# teensy_shield.net
KiCad netlist of a schematic drawn in EAGLE
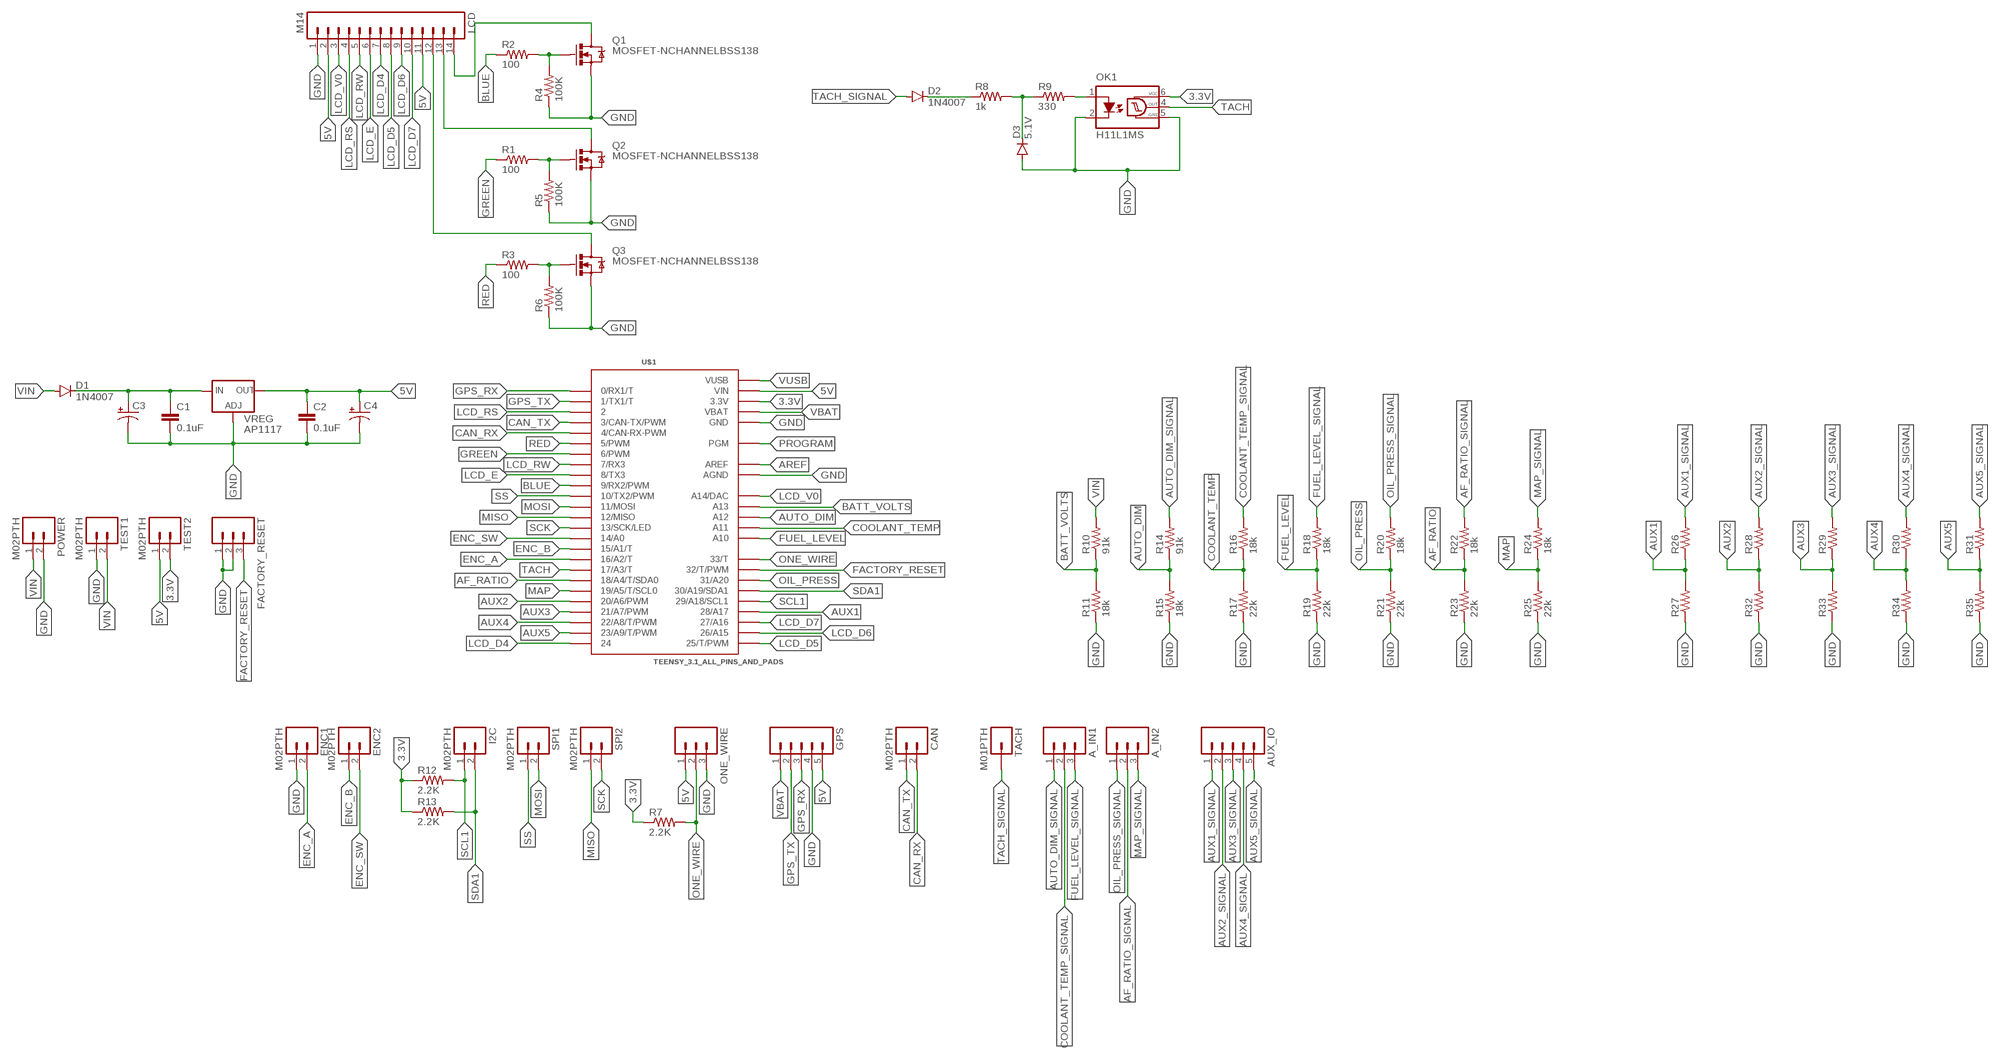
[diagram p0: schematic, sheet 1]

(export (version "E")
  (design (tool "Eeschema 10.0.6"))
  (components
    (comp (ref "AUX_IO")
      (value "M05PTH")
      (footprint "eagle-import:1X05")
      (libsource (lib "eagle-import") (part "M05PTH"))
    )
    (comp (ref "A_IN1")
      (value "M03PTH")
      (footprint "eagle-import:1X03")
      (libsource (lib "eagle-import") (part "M03PTH"))
    )
    (comp (ref "A_IN2")
      (value "M03PTH")
      (footprint "eagle-import:1X03")
      (libsource (lib "eagle-import") (part "M03PTH"))
    )
    (comp (ref "C1")
      (value "0.1uF")
      (footprint "eagle-import:1206")
      (libsource (lib "eagle-import") (part "CAP1206"))
    )
    (comp (ref "C2")
      (value "0.1uF")
      (footprint "eagle-import:1206")
      (libsource (lib "eagle-import") (part "CAP1206"))
    )
    (comp (ref "C3")
      (value "CAP_POL6032")
      (footprint "eagle-import:EIA6032")
      (libsource (lib "eagle-import") (part "CAP_POL6032"))
    )
    (comp (ref "C4")
      (value "CAP_POL6032")
      (footprint "eagle-import:EIA6032")
      (libsource (lib "eagle-import") (part "CAP_POL6032"))
    )
    (comp (ref "CAN")
      (value "M02PTH")
      (footprint "eagle-import:1X02")
      (libsource (lib "eagle-import") (part "M02PTH"))
    )
    (comp (ref "D1")
      (value "1N4007")
      (footprint "eagle-import:SMA-DIODE_ALT")
      (libsource (lib "eagle-import") (part "DIODESMA-ALT"))
    )
    (comp (ref "D2")
      (value "1N4007")
      (footprint "eagle-import:SMA-DIODE_ALT")
      (libsource (lib "eagle-import") (part "DIODESMA-ALT"))
    )
    (comp (ref "D3")
      (value "5.1V")
      (footprint "eagle-import:SMA-DIODE_ALT")
      (libsource (lib "eagle-import") (part "DIODESMA-ALT"))
    )
    (comp (ref "ENC1")
      (value "M02PTH")
      (footprint "eagle-import:1X02")
      (libsource (lib "eagle-import") (part "M02PTH"))
    )
    (comp (ref "ENC2")
      (value "M02PTH")
      (footprint "eagle-import:1X02")
      (libsource (lib "eagle-import") (part "M02PTH"))
    )
    (comp (ref "FACTORY_RESET")
      (value "M03PTH")
      (footprint "eagle-import:1X03")
      (libsource (lib "eagle-import") (part "M03PTH"))
    )
    (comp (ref "GPS")
      (value "M05PTH")
      (footprint "eagle-import:1X05")
      (libsource (lib "eagle-import") (part "M05PTH"))
    )
    (comp (ref "I2C")
      (value "M02PTH")
      (footprint "eagle-import:1X02")
      (libsource (lib "eagle-import") (part "M02PTH"))
    )
    (comp (ref "LCD")
      (value "M14")
      (footprint "eagle-import:1X14")
      (libsource (lib "eagle-import") (part "M14"))
    )
    (comp (ref "OK1")
      (value "H11L1MS")
      (footprint "eagle-import:DIL6-SMD")
      (libsource (lib "eagle-import") (part "H11LMS1"))
    )
    (comp (ref "ONE_WIRE")
      (value "M03PTH")
      (footprint "eagle-import:1X03")
      (libsource (lib "eagle-import") (part "M03PTH"))
    )
    (comp (ref "POWER")
      (value "M02PTH")
      (footprint "eagle-import:1X02")
      (libsource (lib "eagle-import") (part "M02PTH"))
    )
    (comp (ref "Q1")
      (value "MOSFET-NCHANNELBSS138")
      (footprint "eagle-import:SOT23")
      (libsource (lib "eagle-import") (part "MOSFET-NCHANNELBSS138"))
    )
    (comp (ref "Q2")
      (value "MOSFET-NCHANNELBSS138")
      (footprint "eagle-import:SOT23")
      (libsource (lib "eagle-import") (part "MOSFET-NCHANNELBSS138"))
    )
    (comp (ref "Q3")
      (value "MOSFET-NCHANNELBSS138")
      (footprint "eagle-import:SOT23")
      (libsource (lib "eagle-import") (part "MOSFET-NCHANNELBSS138"))
    )
    (comp (ref "R1")
      (value "100")
      (footprint "eagle-import:1206")
      (libsource (lib "eagle-import") (part "RESISTOR1206"))
    )
    (comp (ref "R2")
      (value "100")
      (footprint "eagle-import:1206")
      (libsource (lib "eagle-import") (part "RESISTOR1206"))
    )
    (comp (ref "R3")
      (value "100")
      (footprint "eagle-import:1206")
      (libsource (lib "eagle-import") (part "RESISTOR1206"))
    )
    (comp (ref "R4")
      (value "100K")
      (footprint "eagle-import:1206")
      (libsource (lib "eagle-import") (part "RESISTOR1206"))
    )
    (comp (ref "R5")
      (value "100K")
      (footprint "eagle-import:1206")
      (libsource (lib "eagle-import") (part "RESISTOR1206"))
    )
    (comp (ref "R6")
      (value "100K")
      (footprint "eagle-import:1206")
      (libsource (lib "eagle-import") (part "RESISTOR1206"))
    )
    (comp (ref "R7")
      (value "2.2K")
      (footprint "eagle-import:1206")
      (libsource (lib "eagle-import") (part "RESISTOR1206"))
    )
    (comp (ref "R8")
      (value "1k")
      (footprint "eagle-import:1206")
      (libsource (lib "eagle-import") (part "RESISTOR1206"))
    )
    (comp (ref "R9")
      (value "330")
      (footprint "eagle-import:1206")
      (libsource (lib "eagle-import") (part "RESISTOR1206"))
    )
    (comp (ref "R10")
      (value "91k")
      (footprint "eagle-import:1206")
      (libsource (lib "eagle-import") (part "RESISTOR1206"))
    )
    (comp (ref "R11")
      (value "18k")
      (footprint "eagle-import:1206")
      (libsource (lib "eagle-import") (part "RESISTOR1206"))
    )
    (comp (ref "R12")
      (value "2.2K")
      (footprint "eagle-import:1206")
      (libsource (lib "eagle-import") (part "RESISTOR1206"))
    )
    (comp (ref "R13")
      (value "2.2K")
      (footprint "eagle-import:1206")
      (libsource (lib "eagle-import") (part "RESISTOR1206"))
    )
    (comp (ref "R14")
      (value "91k")
      (footprint "eagle-import:1206")
      (libsource (lib "eagle-import") (part "RESISTOR1206"))
    )
    (comp (ref "R15")
      (value "18k")
      (footprint "eagle-import:1206")
      (libsource (lib "eagle-import") (part "RESISTOR1206"))
    )
    (comp (ref "R16")
      (value "18k")
      (footprint "eagle-import:1206")
      (libsource (lib "eagle-import") (part "RESISTOR1206"))
    )
    (comp (ref "R17")
      (value "22k")
      (footprint "eagle-import:1206")
      (libsource (lib "eagle-import") (part "RESISTOR1206"))
    )
    (comp (ref "R18")
      (value "18k")
      (footprint "eagle-import:1206")
      (libsource (lib "eagle-import") (part "RESISTOR1206"))
    )
    (comp (ref "R19")
      (value "22k")
      (footprint "eagle-import:1206")
      (libsource (lib "eagle-import") (part "RESISTOR1206"))
    )
    (comp (ref "R20")
      (value "18k")
      (footprint "eagle-import:1206")
      (libsource (lib "eagle-import") (part "RESISTOR1206"))
    )
    (comp (ref "R21")
      (value "22k")
      (footprint "eagle-import:1206")
      (libsource (lib "eagle-import") (part "RESISTOR1206"))
    )
    (comp (ref "R22")
      (value "18k")
      (footprint "eagle-import:1206")
      (libsource (lib "eagle-import") (part "RESISTOR1206"))
    )
    (comp (ref "R23")
      (value "22k")
      (footprint "eagle-import:1206")
      (libsource (lib "eagle-import") (part "RESISTOR1206"))
    )
    (comp (ref "R24")
      (value "18k")
      (footprint "eagle-import:1206")
      (libsource (lib "eagle-import") (part "RESISTOR1206"))
    )
    (comp (ref "R25")
      (value "22k")
      (footprint "eagle-import:1206")
      (libsource (lib "eagle-import") (part "RESISTOR1206"))
    )
    (comp (ref "R26")
      (value "RESISTOR1206")
      (footprint "eagle-import:1206")
      (libsource (lib "eagle-import") (part "RESISTOR1206"))
    )
    (comp (ref "R27")
      (value "RESISTOR1206")
      (footprint "eagle-import:1206")
      (libsource (lib "eagle-import") (part "RESISTOR1206"))
    )
    (comp (ref "R28")
      (value "RESISTOR1206")
      (footprint "eagle-import:1206")
      (libsource (lib "eagle-import") (part "RESISTOR1206"))
    )
    (comp (ref "R29")
      (value "RESISTOR1206")
      (footprint "eagle-import:1206")
      (libsource (lib "eagle-import") (part "RESISTOR1206"))
    )
    (comp (ref "R30")
      (value "RESISTOR1206")
      (footprint "eagle-import:1206")
      (libsource (lib "eagle-import") (part "RESISTOR1206"))
    )
    (comp (ref "R31")
      (value "RESISTOR1206")
      (footprint "eagle-import:1206")
      (libsource (lib "eagle-import") (part "RESISTOR1206"))
    )
    (comp (ref "R32")
      (value "RESISTOR1206")
      (footprint "eagle-import:1206")
      (libsource (lib "eagle-import") (part "RESISTOR1206"))
    )
    (comp (ref "R33")
      (value "RESISTOR1206")
      (footprint "eagle-import:1206")
      (libsource (lib "eagle-import") (part "RESISTOR1206"))
    )
    (comp (ref "R34")
      (value "RESISTOR1206")
      (footprint "eagle-import:1206")
      (libsource (lib "eagle-import") (part "RESISTOR1206"))
    )
    (comp (ref "R35")
      (value "RESISTOR1206")
      (footprint "eagle-import:1206")
      (libsource (lib "eagle-import") (part "RESISTOR1206"))
    )
    (comp (ref "SPI1")
      (value "M02PTH")
      (footprint "eagle-import:1X02")
      (libsource (lib "eagle-import") (part "M02PTH"))
    )
    (comp (ref "SPI2")
      (value "M02PTH")
      (footprint "eagle-import:1X02")
      (libsource (lib "eagle-import") (part "M02PTH"))
    )
    (comp (ref "TACH")
      (value "M01PTH")
      (footprint "eagle-import:1X01")
      (libsource (lib "eagle-import") (part "M01PTH"))
    )
    (comp (ref "TEST1")
      (value "M02PTH")
      (footprint "eagle-import:1X02")
      (libsource (lib "eagle-import") (part "M02PTH"))
    )
    (comp (ref "TEST2")
      (value "M02PTH")
      (footprint "eagle-import:1X02")
      (libsource (lib "eagle-import") (part "M02PTH"))
    )
    (comp (ref "U$1")
      (value "TEENSY_3.1_ALL_PINS_AND_PADS")
      (footprint "eagle-import:TEENSY_3.1_ALLPINS")
      (libsource (lib "eagle-import") (part "TEENSY_3.1_ALL_PINS_AND_PADS"))
    )
    (comp (ref "VREG")
      (value "AP1117")
      (footprint "eagle-import:SOT223")
      (libsource (lib "eagle-import") (part "V_REG_317SMD"))
    )
  )
  (nets
    (net (code "1") (name "3.3V") (class "Default")
      (node (ref "OK1") (pin "6") (pinfunction "VCC_6") (pintype "power_in"))
      (node (ref "R12") (pin "1") (pinfunction "1_1") (pintype "passive"))
      (node (ref "R13") (pin "1") (pinfunction "1_1") (pintype "passive"))
      (node (ref "R7") (pin "1") (pinfunction "1_1") (pintype "passive"))
      (node (ref "TEST2") (pin "2") (pinfunction "2_2") (pintype "passive"))
      (node (ref "U$1") (pin "3.3V") (pinfunction "3.3V_3.3V") (pintype "power_in"))
      (node (ref "U$1") (pin "3.3V1") (pinfunction "3.3V_3.3V1") (pintype "power_in"))
      (node (ref "U$1") (pin "3.3V2") (pinfunction "3.3V_3.3V2") (pintype "power_in"))
    )
    (net (code "2") (name "5V") (class "Default")
      (node (ref "C2") (pin "1") (pinfunction "1_1") (pintype "passive"))
      (node (ref "C4") (pin "P$1") (pinfunction "+_P$1") (pintype "passive"))
      (node (ref "GPS") (pin "5") (pinfunction "5_5") (pintype "passive"))
      (node (ref "LCD") (pin "11") (pinfunction "11_11") (pintype "passive"))
      (node (ref "LCD") (pin "2") (pinfunction "2_2") (pintype "passive"))
      (node (ref "ONE_WIRE") (pin "1") (pinfunction "1_1") (pintype "passive"))
      (node (ref "TEST2") (pin "1") (pinfunction "1_1") (pintype "passive"))
      (node (ref "U$1") (pin "VIN") (pinfunction "VIN_VIN") (pintype "power_in"))
      (node (ref "VREG") (pin "2") (pinfunction "OUT_2") (pintype "output"))
    )
    (net (code "3") (name "AF_RATIO") (class "Default")
      (node (ref "R22") (pin "1") (pinfunction "1_1") (pintype "passive"))
      (node (ref "R23") (pin "2") (pinfunction "2_2") (pintype "passive"))
      (node (ref "U$1") (pin "18/A4") (pinfunction "18/A4/T/SDA0_18/A4") (pintype "bidirectional"))
    )
    (net (code "4") (name "AF_RATIO_SIGNAL") (class "Default")
      (node (ref "A_IN2") (pin "2") (pinfunction "2_2") (pintype "passive"))
      (node (ref "R22") (pin "2") (pinfunction "2_2") (pintype "passive"))
    )
    (net (code "5") (name "AREF") (class "Default")
      (node (ref "U$1") (pin "AREF") (pinfunction "AREF_AREF") (pintype "power_in"))
    )
    (net (code "6") (name "AUTO_DIM") (class "Default")
      (node (ref "R14") (pin "1") (pinfunction "1_1") (pintype "passive"))
      (node (ref "R15") (pin "2") (pinfunction "2_2") (pintype "passive"))
      (node (ref "U$1") (pin "A12") (pinfunction "A12_A12") (pintype "bidirectional"))
    )
    (net (code "7") (name "AUTO_DIM_SIGNAL") (class "Default")
      (node (ref "A_IN1") (pin "1") (pinfunction "1_1") (pintype "passive"))
      (node (ref "R14") (pin "2") (pinfunction "2_2") (pintype "passive"))
    )
    (net (code "8") (name "AUX1") (class "Default")
      (node (ref "R26") (pin "1") (pinfunction "1_1") (pintype "passive"))
      (node (ref "R27") (pin "2") (pinfunction "2_2") (pintype "passive"))
      (node (ref "U$1") (pin "28") (pinfunction "28/A17_28") (pintype "bidirectional"))
    )
    (net (code "9") (name "AUX1_SIGNAL") (class "Default")
      (node (ref "AUX_IO") (pin "1") (pinfunction "1_1") (pintype "passive"))
      (node (ref "R26") (pin "2") (pinfunction "2_2") (pintype "passive"))
    )
    (net (code "10") (name "AUX2") (class "Default")
      (node (ref "R28") (pin "1") (pinfunction "1_1") (pintype "passive"))
      (node (ref "R32") (pin "2") (pinfunction "2_2") (pintype "passive"))
      (node (ref "U$1") (pin "20/A6") (pinfunction "20/A6/PWM_20/A6") (pintype "bidirectional"))
    )
    (net (code "11") (name "AUX2_SIGNAL") (class "Default")
      (node (ref "AUX_IO") (pin "2") (pinfunction "2_2") (pintype "passive"))
      (node (ref "R28") (pin "2") (pinfunction "2_2") (pintype "passive"))
    )
    (net (code "12") (name "AUX3") (class "Default")
      (node (ref "R29") (pin "1") (pinfunction "1_1") (pintype "passive"))
      (node (ref "R33") (pin "2") (pinfunction "2_2") (pintype "passive"))
      (node (ref "U$1") (pin "21/A7") (pinfunction "21/A7/PWM_21/A7") (pintype "bidirectional"))
    )
    (net (code "13") (name "AUX3_SIGNAL") (class "Default")
      (node (ref "AUX_IO") (pin "3") (pinfunction "3_3") (pintype "passive"))
      (node (ref "R29") (pin "2") (pinfunction "2_2") (pintype "passive"))
    )
    (net (code "14") (name "AUX4") (class "Default")
      (node (ref "R30") (pin "1") (pinfunction "1_1") (pintype "passive"))
      (node (ref "R34") (pin "2") (pinfunction "2_2") (pintype "passive"))
      (node (ref "U$1") (pin "22/A8") (pinfunction "22/A8/T/PWM_22/A8") (pintype "bidirectional"))
    )
    (net (code "15") (name "AUX4_SIGNAL") (class "Default")
      (node (ref "AUX_IO") (pin "4") (pinfunction "4_4") (pintype "passive"))
      (node (ref "R30") (pin "2") (pinfunction "2_2") (pintype "passive"))
    )
    (net (code "16") (name "AUX5") (class "Default")
      (node (ref "R31") (pin "1") (pinfunction "1_1") (pintype "passive"))
      (node (ref "R35") (pin "2") (pinfunction "2_2") (pintype "passive"))
      (node (ref "U$1") (pin "23/A9") (pinfunction "23/A9/T/PWM_23/A9") (pintype "bidirectional"))
    )
    (net (code "17") (name "AUX5_SIGNAL") (class "Default")
      (node (ref "AUX_IO") (pin "5") (pinfunction "5_5") (pintype "passive"))
      (node (ref "R31") (pin "2") (pinfunction "2_2") (pintype "passive"))
    )
    (net (code "18") (name "BATT_VOLTS") (class "Default")
      (node (ref "R10") (pin "1") (pinfunction "1_1") (pintype "passive"))
      (node (ref "R11") (pin "2") (pinfunction "2_2") (pintype "passive"))
      (node (ref "U$1") (pin "A13") (pinfunction "A13_A13") (pintype "bidirectional"))
    )
    (net (code "19") (name "BLUE") (class "Default")
      (node (ref "R2") (pin "1") (pinfunction "1_1") (pintype "passive"))
      (node (ref "U$1") (pin "9") (pinfunction "9/RX2/PWM_9") (pintype "bidirectional"))
    )
    (net (code "20") (name "CAN_RX") (class "Default")
      (node (ref "CAN") (pin "2") (pinfunction "2_2") (pintype "passive"))
      (node (ref "U$1") (pin "4") (pinfunction "4/CAN-RX-PWM_4") (pintype "bidirectional"))
    )
    (net (code "21") (name "CAN_TX") (class "Default")
      (node (ref "CAN") (pin "1") (pinfunction "1_1") (pintype "passive"))
      (node (ref "U$1") (pin "3") (pinfunction "3/CAN-TX/PWM_3") (pintype "bidirectional"))
    )
    (net (code "22") (name "COOLANT_TEMP") (class "Default")
      (node (ref "R16") (pin "1") (pinfunction "1_1") (pintype "passive"))
      (node (ref "R17") (pin "2") (pinfunction "2_2") (pintype "passive"))
      (node (ref "U$1") (pin "A11") (pinfunction "A11_A11") (pintype "bidirectional"))
    )
    (net (code "23") (name "COOLANT_TEMP_SIGNAL") (class "Default")
      (node (ref "A_IN1") (pin "2") (pinfunction "2_2") (pintype "passive"))
      (node (ref "R16") (pin "2") (pinfunction "2_2") (pintype "passive"))
    )
    (net (code "24") (name "ENC_A") (class "Default")
      (node (ref "ENC1") (pin "2") (pinfunction "2_2") (pintype "passive"))
      (node (ref "U$1") (pin "16/A2") (pinfunction "16/A2/T_16/A2") (pintype "bidirectional"))
    )
    (net (code "25") (name "ENC_B") (class "Default")
      (node (ref "ENC2") (pin "1") (pinfunction "1_1") (pintype "passive"))
      (node (ref "U$1") (pin "15/A1") (pinfunction "15/A1/T_15/A1") (pintype "bidirectional"))
    )
    (net (code "26") (name "ENC_SW") (class "Default")
      (node (ref "ENC2") (pin "2") (pinfunction "2_2") (pintype "passive"))
      (node (ref "U$1") (pin "14/A0") (pinfunction "14/A0_14/A0") (pintype "bidirectional"))
    )
    (net (code "27") (name "FACTORY_RESET") (class "Default")
      (node (ref "FACTORY_RESET") (pin "3") (pinfunction "3_3") (pintype "passive"))
      (node (ref "U$1") (pin "32") (pinfunction "32/T/PWM_32") (pintype "bidirectional"))
    )
    (net (code "28") (name "FUEL_LEVEL") (class "Default")
      (node (ref "R18") (pin "1") (pinfunction "1_1") (pintype "passive"))
      (node (ref "R19") (pin "2") (pinfunction "2_2") (pintype "passive"))
      (node (ref "U$1") (pin "A10") (pinfunction "A10_A10") (pintype "bidirectional"))
    )
    (net (code "29") (name "FUEL_LEVEL_SIGNAL") (class "Default")
      (node (ref "A_IN1") (pin "3") (pinfunction "3_3") (pintype "passive"))
      (node (ref "R18") (pin "2") (pinfunction "2_2") (pintype "passive"))
    )
    (net (code "30") (name "GND") (class "Default")
      (node (ref "C1") (pin "2") (pinfunction "2_2") (pintype "passive"))
      (node (ref "C2") (pin "2") (pinfunction "2_2") (pintype "passive"))
      (node (ref "C3") (pin "P$2") (pinfunction "-_P$2") (pintype "passive"))
      (node (ref "C4") (pin "P$2") (pinfunction "-_P$2") (pintype "passive"))
      (node (ref "D3") (pin "A") (pinfunction "A_A") (pintype "passive"))
      (node (ref "ENC1") (pin "1") (pinfunction "1_1") (pintype "passive"))
      (node (ref "FACTORY_RESET") (pin "1") (pinfunction "1_1") (pintype "passive"))
      (node (ref "FACTORY_RESET") (pin "2") (pinfunction "2_2") (pintype "passive"))
      (node (ref "GPS") (pin "4") (pinfunction "4_4") (pintype "passive"))
      (node (ref "LCD") (pin "1") (pinfunction "1_1") (pintype "passive"))
      (node (ref "OK1") (pin "2") (pinfunction "C_2") (pintype "passive"))
      (node (ref "OK1") (pin "5") (pinfunction "GND_5") (pintype "power_in"))
      (node (ref "ONE_WIRE") (pin "3") (pinfunction "3_3") (pintype "passive"))
      (node (ref "POWER") (pin "2") (pinfunction "2_2") (pintype "passive"))
      (node (ref "Q1") (pin "2") (pinfunction "S_2") (pintype "passive"))
      (node (ref "Q2") (pin "2") (pinfunction "S_2") (pintype "passive"))
      (node (ref "Q3") (pin "2") (pinfunction "S_2") (pintype "passive"))
      (node (ref "R11") (pin "1") (pinfunction "1_1") (pintype "passive"))
      (node (ref "R15") (pin "1") (pinfunction "1_1") (pintype "passive"))
      (node (ref "R17") (pin "1") (pinfunction "1_1") (pintype "passive"))
      (node (ref "R19") (pin "1") (pinfunction "1_1") (pintype "passive"))
      (node (ref "R21") (pin "1") (pinfunction "1_1") (pintype "passive"))
      (node (ref "R23") (pin "1") (pinfunction "1_1") (pintype "passive"))
      (node (ref "R25") (pin "1") (pinfunction "1_1") (pintype "passive"))
      (node (ref "R27") (pin "1") (pinfunction "1_1") (pintype "passive"))
      (node (ref "R32") (pin "1") (pinfunction "1_1") (pintype "passive"))
      (node (ref "R33") (pin "1") (pinfunction "1_1") (pintype "passive"))
      (node (ref "R34") (pin "1") (pinfunction "1_1") (pintype "passive"))
      (node (ref "R35") (pin "1") (pinfunction "1_1") (pintype "passive"))
      (node (ref "R4") (pin "1") (pinfunction "1_1") (pintype "passive"))
      (node (ref "R5") (pin "1") (pinfunction "1_1") (pintype "passive"))
      (node (ref "R6") (pin "1") (pinfunction "1_1") (pintype "passive"))
      (node (ref "TEST1") (pin "1") (pinfunction "1_1") (pintype "passive"))
      (node (ref "U$1") (pin "AGND") (pinfunction "AGND_AGND") (pintype "power_in"))
      (node (ref "U$1") (pin "GND") (pinfunction "GND_GND") (pintype "power_in"))
      (node (ref "U$1") (pin "GND1") (pinfunction "GND_GND1") (pintype "power_in"))
      (node (ref "U$1") (pin "GND2") (pinfunction "GND_GND2") (pintype "power_in"))
      (node (ref "VREG") (pin "1") (pinfunction "ADJ_1") (pintype "input"))
    )
    (net (code "31") (name "GPS_RX") (class "Default")
      (node (ref "GPS") (pin "3") (pinfunction "3_3") (pintype "passive"))
      (node (ref "U$1") (pin "0") (pinfunction "0/RX1/T_0") (pintype "bidirectional"))
    )
    (net (code "32") (name "GPS_TX") (class "Default")
      (node (ref "GPS") (pin "2") (pinfunction "2_2") (pintype "passive"))
      (node (ref "U$1") (pin "1") (pinfunction "1/TX1/T_1") (pintype "bidirectional"))
    )
    (net (code "33") (name "GREEN") (class "Default")
      (node (ref "R1") (pin "1") (pinfunction "1_1") (pintype "passive"))
      (node (ref "U$1") (pin "6") (pinfunction "6/PWM_6") (pintype "bidirectional"))
    )
    (net (code "34") (name "LCD_D4") (class "Default")
      (node (ref "LCD") (pin "7") (pinfunction "7_7") (pintype "passive"))
      (node (ref "U$1") (pin "24") (pinfunction "24_24") (pintype "bidirectional"))
    )
    (net (code "35") (name "LCD_D5") (class "Default")
      (node (ref "LCD") (pin "8") (pinfunction "8_8") (pintype "passive"))
      (node (ref "U$1") (pin "25") (pinfunction "25/T/PWM_25") (pintype "bidirectional"))
    )
    (net (code "36") (name "LCD_D6") (class "Default")
      (node (ref "LCD") (pin "9") (pinfunction "9_9") (pintype "passive"))
      (node (ref "U$1") (pin "26") (pinfunction "26/A15_26") (pintype "bidirectional"))
    )
    (net (code "37") (name "LCD_D7") (class "Default")
      (node (ref "LCD") (pin "10") (pinfunction "10_10") (pintype "passive"))
      (node (ref "U$1") (pin "27") (pinfunction "27/A16_27") (pintype "bidirectional"))
    )
    (net (code "38") (name "LCD_E") (class "Default")
      (node (ref "LCD") (pin "6") (pinfunction "6_6") (pintype "passive"))
      (node (ref "U$1") (pin "8") (pinfunction "8/TX3_8") (pintype "bidirectional"))
    )
    (net (code "39") (name "LCD_RS") (class "Default")
      (node (ref "LCD") (pin "4") (pinfunction "4_4") (pintype "passive"))
      (node (ref "U$1") (pin "2") (pinfunction "2_2") (pintype "bidirectional"))
    )
    (net (code "40") (name "LCD_RW") (class "Default")
      (node (ref "LCD") (pin "5") (pinfunction "5_5") (pintype "passive"))
      (node (ref "U$1") (pin "7") (pinfunction "7/RX3_7") (pintype "bidirectional"))
    )
    (net (code "41") (name "LCD_V0") (class "Default")
      (node (ref "LCD") (pin "3") (pinfunction "3_3") (pintype "passive"))
      (node (ref "U$1") (pin "A14") (pinfunction "A14/DAC_A14") (pintype "bidirectional"))
    )
    (net (code "42") (name "MAP") (class "Default")
      (node (ref "R24") (pin "1") (pinfunction "1_1") (pintype "passive"))
      (node (ref "R25") (pin "2") (pinfunction "2_2") (pintype "passive"))
      (node (ref "U$1") (pin "19/A5") (pinfunction "19/A5/T/SCL0_19/A5") (pintype "bidirectional"))
    )
    (net (code "43") (name "MAP_SIGNAL") (class "Default")
      (node (ref "A_IN2") (pin "3") (pinfunction "3_3") (pintype "passive"))
      (node (ref "R24") (pin "2") (pinfunction "2_2") (pintype "passive"))
    )
    (net (code "44") (name "MISO") (class "Default")
      (node (ref "SPI2") (pin "1") (pinfunction "1_1") (pintype "passive"))
      (node (ref "U$1") (pin "12") (pinfunction "12/MISO_12") (pintype "bidirectional"))
    )
    (net (code "45") (name "MOSI") (class "Default")
      (node (ref "SPI1") (pin "2") (pinfunction "2_2") (pintype "passive"))
      (node (ref "U$1") (pin "11") (pinfunction "11/MOSI_11") (pintype "bidirectional"))
    )
    (net (code "46") (name "Net-(C3-+)") (class "Default")
      (node (ref "C1") (pin "1") (pinfunction "1_1") (pintype "passive"))
      (node (ref "C3") (pin "P$1") (pinfunction "+_P$1") (pintype "passive"))
      (node (ref "D1") (pin "C") (pinfunction "C_C") (pintype "passive"))
      (node (ref "VREG") (pin "3") (pinfunction "IN_3") (pintype "input"))
    )
    (net (code "47") (name "Net-(D2-PadC)") (class "Default")
      (node (ref "D2") (pin "C") (pinfunction "C_C") (pintype "passive"))
      (node (ref "R8") (pin "1") (pinfunction "1_1") (pintype "passive"))
    )
    (net (code "48") (name "Net-(D3-PadC)") (class "Default")
      (node (ref "D3") (pin "C") (pinfunction "C_C") (pintype "passive"))
      (node (ref "R8") (pin "2") (pinfunction "2_2") (pintype "passive"))
      (node (ref "R9") (pin "1") (pinfunction "1_1") (pintype "passive"))
    )
    (net (code "49") (name "Net-(OK1-A)") (class "Default")
      (node (ref "OK1") (pin "1") (pinfunction "A_1") (pintype "passive"))
      (node (ref "R9") (pin "2") (pinfunction "2_2") (pintype "passive"))
    )
    (net (code "50") (name "Net-(Q1-D)") (class "Default")
      (node (ref "LCD") (pin "14") (pinfunction "14_14") (pintype "passive"))
      (node (ref "Q1") (pin "3") (pinfunction "D_3") (pintype "passive"))
    )
    (net (code "51") (name "Net-(Q1-G)") (class "Default")
      (node (ref "Q1") (pin "1") (pinfunction "G_1") (pintype "passive"))
      (node (ref "R2") (pin "2") (pinfunction "2_2") (pintype "passive"))
      (node (ref "R4") (pin "2") (pinfunction "2_2") (pintype "passive"))
    )
    (net (code "52") (name "Net-(Q2-D)") (class "Default")
      (node (ref "LCD") (pin "13") (pinfunction "13_13") (pintype "passive"))
      (node (ref "Q2") (pin "3") (pinfunction "D_3") (pintype "passive"))
    )
    (net (code "53") (name "Net-(Q2-G)") (class "Default")
      (node (ref "Q2") (pin "1") (pinfunction "G_1") (pintype "passive"))
      (node (ref "R1") (pin "2") (pinfunction "2_2") (pintype "passive"))
      (node (ref "R5") (pin "2") (pinfunction "2_2") (pintype "passive"))
    )
    (net (code "54") (name "Net-(Q3-D)") (class "Default")
      (node (ref "LCD") (pin "12") (pinfunction "12_12") (pintype "passive"))
      (node (ref "Q3") (pin "3") (pinfunction "D_3") (pintype "passive"))
    )
    (net (code "55") (name "Net-(Q3-G)") (class "Default")
      (node (ref "Q3") (pin "1") (pinfunction "G_1") (pintype "passive"))
      (node (ref "R3") (pin "2") (pinfunction "2_2") (pintype "passive"))
      (node (ref "R6") (pin "2") (pinfunction "2_2") (pintype "passive"))
    )
    (net (code "56") (name "OIL_PRESS") (class "Default")
      (node (ref "R20") (pin "1") (pinfunction "1_1") (pintype "passive"))
      (node (ref "R21") (pin "2") (pinfunction "2_2") (pintype "passive"))
      (node (ref "U$1") (pin "31") (pinfunction "31/A20_31") (pintype "bidirectional"))
    )
    (net (code "57") (name "OIL_PRESS_SIGNAL") (class "Default")
      (node (ref "A_IN2") (pin "1") (pinfunction "1_1") (pintype "passive"))
      (node (ref "R20") (pin "2") (pinfunction "2_2") (pintype "passive"))
    )
    (net (code "58") (name "ONE_WIRE") (class "Default")
      (node (ref "ONE_WIRE") (pin "2") (pinfunction "2_2") (pintype "passive"))
      (node (ref "R7") (pin "2") (pinfunction "2_2") (pintype "passive"))
      (node (ref "U$1") (pin "33") (pinfunction "33/T_33") (pintype "bidirectional"))
    )
    (net (code "59") (name "PROGRAM") (class "Default")
      (node (ref "U$1") (pin "PGM") (pinfunction "PGM_PGM") (pintype "bidirectional"))
    )
    (net (code "60") (name "RED") (class "Default")
      (node (ref "R3") (pin "1") (pinfunction "1_1") (pintype "passive"))
      (node (ref "U$1") (pin "5") (pinfunction "5/PWM_5") (pintype "bidirectional"))
    )
    (net (code "61") (name "SCK") (class "Default")
      (node (ref "SPI2") (pin "2") (pinfunction "2_2") (pintype "passive"))
      (node (ref "U$1") (pin "13") (pinfunction "13/SCK/LED_13") (pintype "bidirectional"))
    )
    (net (code "62") (name "SCL1") (class "Default")
      (node (ref "I2C") (pin "1") (pinfunction "1_1") (pintype "passive"))
      (node (ref "R12") (pin "2") (pinfunction "2_2") (pintype "passive"))
      (node (ref "U$1") (pin "29") (pinfunction "29/A18/SCL1_29") (pintype "bidirectional"))
    )
    (net (code "63") (name "SDA1") (class "Default")
      (node (ref "I2C") (pin "2") (pinfunction "2_2") (pintype "passive"))
      (node (ref "R13") (pin "2") (pinfunction "2_2") (pintype "passive"))
      (node (ref "U$1") (pin "30") (pinfunction "30/A19/SDA1_30") (pintype "bidirectional"))
    )
    (net (code "64") (name "SS") (class "Default")
      (node (ref "SPI1") (pin "1") (pinfunction "1_1") (pintype "passive"))
      (node (ref "U$1") (pin "10") (pinfunction "10/TX2/PWM_10") (pintype "bidirectional"))
    )
    (net (code "65") (name "TACH") (class "Default")
      (node (ref "OK1") (pin "4") (pinfunction "OUT_4") (pintype "output"))
      (node (ref "U$1") (pin "17/A3") (pinfunction "17/A3/T_17/A3") (pintype "bidirectional"))
    )
    (net (code "66") (name "TACH_SIGNAL") (class "Default")
      (node (ref "D2") (pin "A") (pinfunction "A_A") (pintype "passive"))
      (node (ref "TACH") (pin "1") (pinfunction "1_1") (pintype "passive"))
    )
    (net (code "67") (name "VBAT") (class "Default")
      (node (ref "GPS") (pin "1") (pinfunction "1_1") (pintype "passive"))
      (node (ref "U$1") (pin "VBAT") (pinfunction "VBAT_VBAT") (pintype "power_in"))
    )
    (net (code "68") (name "VIN") (class "Default")
      (node (ref "D1") (pin "A") (pinfunction "A_A") (pintype "passive"))
      (node (ref "POWER") (pin "1") (pinfunction "1_1") (pintype "passive"))
      (node (ref "R10") (pin "2") (pinfunction "2_2") (pintype "passive"))
      (node (ref "TEST1") (pin "2") (pinfunction "2_2") (pintype "passive"))
    )
    (net (code "69") (name "VUSB") (class "Default")
      (node (ref "U$1") (pin "VUSB") (pinfunction "VUSB_VUSB") (pintype "power_in"))
    )
  )
)
